# EMG_FSR.net
KiCad netlist of a schematic drawn in EAGLE
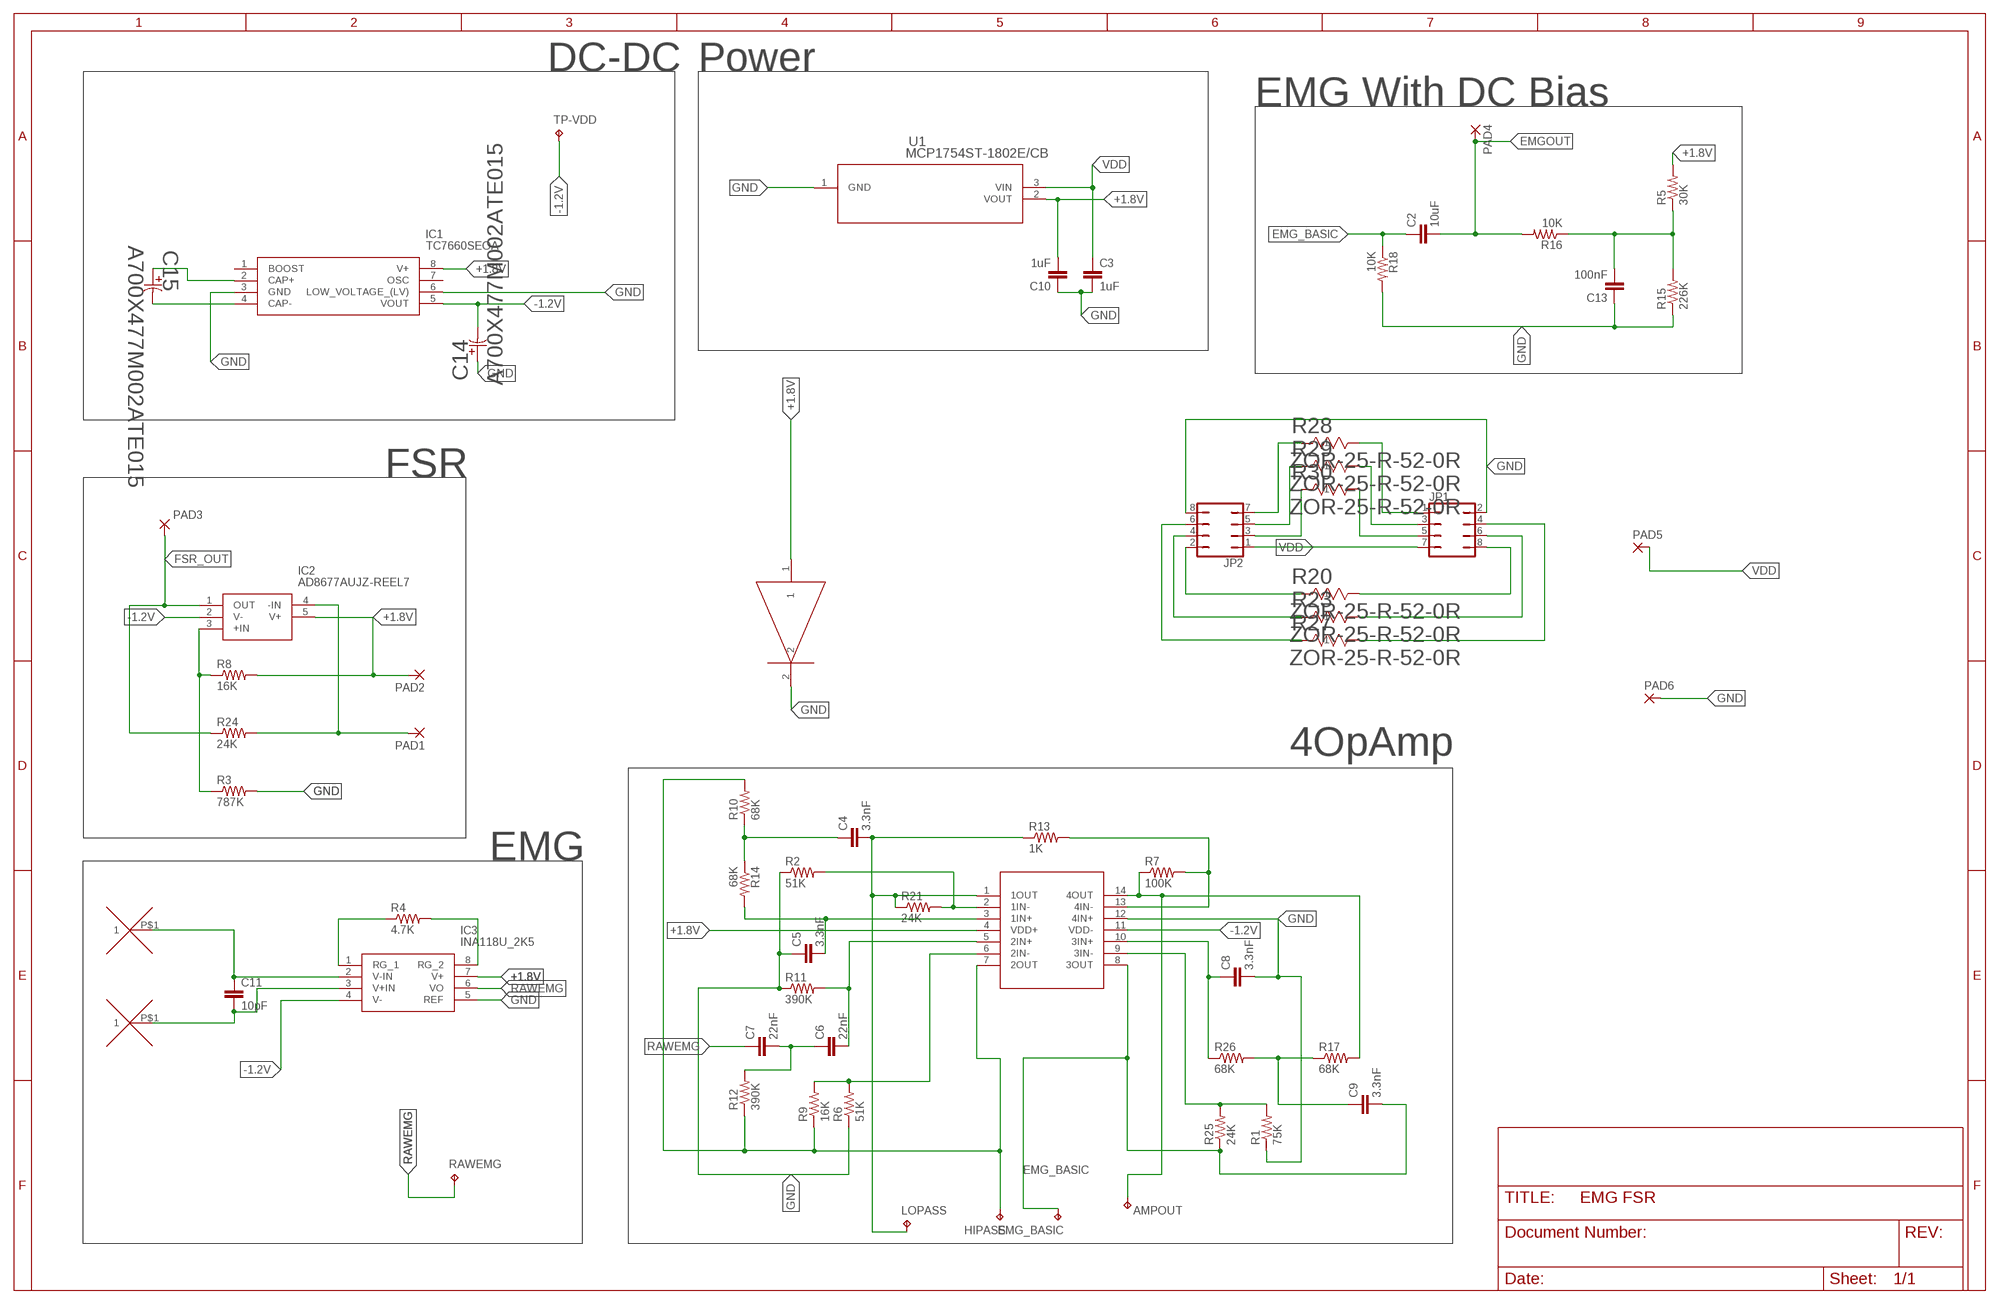
[diagram p0: schematic, sheet 1]

(export (version "E")
  (design (tool "Eeschema 10.0.6"))
  (components
    (comp (ref "AMPOUT")
      (value "TPTP08R")
      (footprint "eagle-import:TP08R")
      (libsource (lib "eagle-import") (part "TPTP08R"))
    )
    (comp (ref "C2")
      (value "10uF")
      (footprint "eagle-import:C0402")
      (libsource (lib "eagle-import") (part "rcl_334_C-EUC0402"))
    )
    (comp (ref "C3")
      (value "1uF")
      (footprint "eagle-import:C0402")
      (libsource (lib "eagle-import") (part "rcl_334_C-EUC0402"))
    )
    (comp (ref "C4")
      (value "3.3nF")
      (footprint "eagle-import:C1206")
      (libsource (lib "eagle-import") (part "C-EUC1206"))
    )
    (comp (ref "C5")
      (value "3.3nF")
      (footprint "eagle-import:C1206")
      (libsource (lib "eagle-import") (part "C-EUC1206"))
    )
    (comp (ref "C6")
      (value "22nF")
      (footprint "eagle-import:C0805")
      (libsource (lib "eagle-import") (part "C-EUC0805"))
    )
    (comp (ref "C7")
      (value "22nF")
      (footprint "eagle-import:C0805")
      (libsource (lib "eagle-import") (part "C-EUC0805"))
    )
    (comp (ref "C8")
      (value "3.3nF")
      (footprint "eagle-import:C1206")
      (libsource (lib "eagle-import") (part "C-EUC1206"))
    )
    (comp (ref "C9")
      (value "3.3nF")
      (footprint "eagle-import:C1206")
      (libsource (lib "eagle-import") (part "C-EUC1206"))
    )
    (comp (ref "C10")
      (value "1uF")
      (footprint "eagle-import:C0402")
      (libsource (lib "eagle-import") (part "rcl_334_C-EUC0402"))
    )
    (comp (ref "C11")
      (value "10pF")
      (footprint "eagle-import:C0402")
      (libsource (lib "eagle-import") (part "rcl_334_C-EUC0402"))
    )
    (comp (ref "C13")
      (value "100nF")
      (footprint "eagle-import:C0402")
      (libsource (lib "eagle-import") (part "rcl_334_C-EUC0402"))
    )
    (comp (ref "C14")
      (value "A700X477M002ATE015")
      (footprint "eagle-import:PCAP7343-43_KEMET_KEM")
      (libsource (lib "eagle-import") (part "A700X477M002ATE015"))
    )
    (comp (ref "C15")
      (value "A700X477M002ATE015")
      (footprint "eagle-import:PCAP7343-43_KEMET_KEM")
      (libsource (lib "eagle-import") (part "A700X477M002ATE015"))
    )
    (comp (ref "EMG_BASIC")
      (value "TPTP08R")
      (footprint "eagle-import:TP08R")
      (libsource (lib "eagle-import") (part "TPTP08R"))
    )
    (comp (ref "HIPASS")
      (value "TPTP08R")
      (footprint "eagle-import:TP08R")
      (libsource (lib "eagle-import") (part "TPTP08R"))
    )
    (comp (ref "IC1")
      (value "TC7660SEOA")
      (footprint "eagle-import:SOIC127P600X175-8N")
      (fields (field (name "MOUSER_PART_NUMBER") "579-TC7660SEOA"))
      (libsource (lib "eagle-import") (part "TC7660SEOA"))
    )
    (comp (ref "IC2")
      (value "AD8677AUJZ-REEL7")
      (footprint "eagle-import:SOT95P280X100-5N")
      (fields (field (name "MOUSER_PART_NUMBER") "584-AD8677AUJZ-R7"))
      (libsource (lib "eagle-import") (part "AD8677AUJZ-REEL7"))
    )
    (comp (ref "IC3")
      (value "INA118U_2K5")
      (footprint "eagle-import:SOIC127P600X175-8N")
      (fields
        (field (name "ARROW_PART_NUMBER") "INA118U/2K5")
        (field (name "MOUSER_PART_NUMBER") "595-INA118U/2K5")
      )
      (libsource (lib "eagle-import") (part "INA118U_2K5"))
    )
    (comp (ref "JP1")
      (value "JP4Q")
      (footprint "eagle-import:JP4Q")
      (libsource (lib "eagle-import") (part "JP4Q"))
    )
    (comp (ref "JP2")
      (value "JP4Q")
      (footprint "eagle-import:JP4Q")
      (libsource (lib "eagle-import") (part "JP4Q"))
    )
    (comp (ref "LOPASS")
      (value "TPTP08R")
      (footprint "eagle-import:TP08R")
      (libsource (lib "eagle-import") (part "TPTP08R"))
    )
    (comp (ref "PAD1")
      (value "SMD2")
      (footprint "eagle-import:SMD1,27-2,54")
      (libsource (lib "eagle-import") (part "SMD2"))
    )
    (comp (ref "PAD2")
      (value "SMD2")
      (footprint "eagle-import:SMD1,27-2,54")
      (libsource (lib "eagle-import") (part "SMD2"))
    )
    (comp (ref "PAD3")
      (value "1,6/0,8")
      (footprint "eagle-import:1,6_0,8")
      (libsource (lib "eagle-import") (part "1,6/0,8"))
    )
    (comp (ref "PAD4")
      (value "1,6/0,8")
      (footprint "eagle-import:1,6_0,8")
      (libsource (lib "eagle-import") (part "1,6/0,8"))
    )
    (comp (ref "PAD5")
      (value "1,6/0,8")
      (footprint "eagle-import:1,6_0,8")
      (libsource (lib "eagle-import") (part "1,6/0,8"))
    )
    (comp (ref "PAD6")
      (value "1,6/0,8")
      (footprint "eagle-import:1,6_0,8")
      (libsource (lib "eagle-import") (part "1,6/0,8"))
    )
    (comp (ref "R1")
      (value "75K")
      (footprint "eagle-import:R0402")
      (libsource (lib "eagle-import") (part "adafruit_420_R-US_R0402"))
    )
    (comp (ref "R2")
      (value "51K")
      (footprint "eagle-import:R0402")
      (libsource (lib "eagle-import") (part "adafruit_420_R-US_R0402"))
    )
    (comp (ref "R3")
      (value "787K")
      (footprint "eagle-import:R0805")
      (libsource (lib "eagle-import") (part "rcl_R-US_R0805"))
    )
    (comp (ref "R4")
      (value "4.7K")
      (footprint "eagle-import:R0402")
      (libsource (lib "eagle-import") (part "adafruit@1_R-US_R0402"))
    )
    (comp (ref "R5")
      (value "30K")
      (footprint "eagle-import:R0402")
      (libsource (lib "eagle-import") (part "adafruit_420_R-US_R0402"))
    )
    (comp (ref "R6")
      (value "51K")
      (footprint "eagle-import:R0402")
      (libsource (lib "eagle-import") (part "adafruit_420_R-US_R0402"))
    )
    (comp (ref "R7")
      (value "100K")
      (footprint "eagle-import:R1005")
      (libsource (lib "eagle-import") (part "adafruit@1_R-US_R1005"))
    )
    (comp (ref "R8")
      (value "16K")
      (footprint "eagle-import:R0402")
      (libsource (lib "eagle-import") (part "adafruit_420_R-US_R0402"))
    )
    (comp (ref "R9")
      (value "16K")
      (footprint "eagle-import:R0402")
      (libsource (lib "eagle-import") (part "adafruit_420_R-US_R0402"))
    )
    (comp (ref "R10")
      (value "68K")
      (footprint "eagle-import:R0402")
      (libsource (lib "eagle-import") (part "adafruit_420_R-US_R0402"))
    )
    (comp (ref "R11")
      (value "390K")
      (footprint "eagle-import:R0603")
      (libsource (lib "eagle-import") (part "R-US_R0603"))
    )
    (comp (ref "R12")
      (value "390K")
      (footprint "eagle-import:R0603")
      (libsource (lib "eagle-import") (part "adafruit@1_R-US_R0603"))
    )
    (comp (ref "R13")
      (value "1K")
      (footprint "eagle-import:R0402")
      (libsource (lib "eagle-import") (part "adafruit_420_R-US_R0402"))
    )
    (comp (ref "R14")
      (value "68K")
      (footprint "eagle-import:R0402")
      (libsource (lib "eagle-import") (part "adafruit_420_R-US_R0402"))
    )
    (comp (ref "R15")
      (value "226K")
      (footprint "eagle-import:R0402")
      (libsource (lib "eagle-import") (part "adafruit_420_R-US_R0402"))
    )
    (comp (ref "R16")
      (value "10K")
      (footprint "eagle-import:R0402")
      (libsource (lib "eagle-import") (part "adafruit_420_R-US_R0402"))
    )
    (comp (ref "R17")
      (value "68K")
      (footprint "eagle-import:R0402")
      (libsource (lib "eagle-import") (part "adafruit_420_R-US_R0402"))
    )
    (comp (ref "R18")
      (value "10K")
      (footprint "eagle-import:R0402")
      (libsource (lib "eagle-import") (part "adafruit_420_R-US_R0402"))
    )
    (comp (ref "R20")
      (value "ZOR-25-R-52-0R")
      (footprint "eagle-import:RES_ZOR25_6P3X2P3_YAG")
      (fields (field (name "COPYRIGHT") "Copyright (C) 2018 Accelerated Designs. All rights reserved"))
      (libsource (lib "eagle-import") (part "ZOR-25-R-52-0R"))
    )
    (comp (ref "R21")
      (value "24K")
      (footprint "eagle-import:R0402")
      (libsource (lib "eagle-import") (part "adafruit_420_R-US_R0402"))
    )
    (comp (ref "R23")
      (value "ZOR-25-R-52-0R")
      (footprint "eagle-import:RES_ZOR25_6P3X2P3_YAG")
      (fields (field (name "COPYRIGHT") "Copyright (C) 2018 Accelerated Designs. All rights reserved"))
      (libsource (lib "eagle-import") (part "ZOR-25-R-52-0R"))
    )
    (comp (ref "R24")
      (value "24K")
      (footprint "eagle-import:R0402")
      (libsource (lib "eagle-import") (part "adafruit_420_R-US_R0402"))
    )
    (comp (ref "R25")
      (value "24K")
      (footprint "eagle-import:R0402")
      (libsource (lib "eagle-import") (part "adafruit_420_R-US_R0402"))
    )
    (comp (ref "R26")
      (value "68K")
      (footprint "eagle-import:R0402")
      (libsource (lib "eagle-import") (part "adafruit_420_R-US_R0402"))
    )
    (comp (ref "R27")
      (value "ZOR-25-R-52-0R")
      (footprint "eagle-import:RES_ZOR25_6P3X2P3_YAG")
      (fields (field (name "COPYRIGHT") "Copyright (C) 2018 Accelerated Designs. All rights reserved"))
      (libsource (lib "eagle-import") (part "ZOR-25-R-52-0R"))
    )
    (comp (ref "R28")
      (value "ZOR-25-R-52-0R")
      (footprint "eagle-import:RES_ZOR25_6P3X2P3_YAG")
      (fields (field (name "COPYRIGHT") "Copyright (C) 2018 Accelerated Designs. All rights reserved"))
      (libsource (lib "eagle-import") (part "ZOR-25-R-52-0R"))
    )
    (comp (ref "R29")
      (value "ZOR-25-R-52-0R")
      (footprint "eagle-import:RES_ZOR25_6P3X2P3_YAG")
      (fields (field (name "COPYRIGHT") "Copyright (C) 2018 Accelerated Designs. All rights reserved"))
      (libsource (lib "eagle-import") (part "ZOR-25-R-52-0R"))
    )
    (comp (ref "R30")
      (value "ZOR-25-R-52-0R")
      (footprint "eagle-import:RES_ZOR25_6P3X2P3_YAG")
      (fields (field (name "COPYRIGHT") "Copyright (C) 2018 Accelerated Designs. All rights reserved"))
      (libsource (lib "eagle-import") (part "ZOR-25-R-52-0R"))
    )
    (comp (ref "RAWEMG")
      (value "TPTP08R")
      (footprint "eagle-import:TP08R")
      (libsource (lib "eagle-import") (part "TPTP08R"))
    )
    (comp (ref "RED")
      (value "RESC0402X40N")
      (footprint "eagle-import:RESC0402X40N")
      (fields (field (name "MANUFACTURER") "KOA"))
      (libsource (lib "eagle-import") (part "RESC0402X40N"))
    )
    (comp (ref "TP-VDD")
      (value "TPTP08R")
      (footprint "eagle-import:TP08R")
      (libsource (lib "eagle-import") (part "TPTP08R"))
    )
    (comp (ref "U$1")
      (value "TLC2274-HT")
      (footprint "eagle-import:SOP65P640X120-14N")
      (libsource (lib "eagle-import") (part "TLC2274-HT"))
    )
    (comp (ref "U$2")
      (value "EMG_VIA")
      (footprint "eagle-import:EMG_VIA")
      (libsource (lib "eagle-import") (part "EMG_VIA"))
    )
    (comp (ref "U$3")
      (value "EMG_VIA")
      (footprint "eagle-import:EMG_VIA")
      (libsource (lib "eagle-import") (part "EMG_VIA"))
    )
    (comp (ref "U1")
      (value "MCP1754ST-1802E/CB")
      (footprint "eagle-import:SOT-23A_MC_MCH")
      (fields (field (name "COPYRIGHT") "Copyright (C) 2018 Accelerated Designs. All rights reserved"))
      (libsource (lib "eagle-import") (part "MCP1754ST-1802E/CB"))
    )
  )
  (nets
    (net (code "1") (name "+1.8V") (class "Default")
      (node (ref "C10") (pin "2") (pinfunction "2_2") (pintype "passive"))
      (node (ref "IC1") (pin "8") (pinfunction "V+_8") (pintype "bidirectional"))
      (node (ref "IC2") (pin "5") (pinfunction "V+_5") (pintype "bidirectional"))
      (node (ref "IC3") (pin "7") (pinfunction "V+_7") (pintype "bidirectional"))
      (node (ref "PAD2") (pin "1") (pinfunction "P_1") (pintype "passive"))
      (node (ref "R5") (pin "2") (pinfunction "2_2") (pintype "passive"))
      (node (ref "R8") (pin "2") (pinfunction "2_2") (pintype "passive"))
      (node (ref "RED") (pin "1") (pinfunction "1_1") (pintype "bidirectional"))
      (node (ref "U$1") (pin "4") (pinfunction "VDD+_4") (pintype "bidirectional"))
      (node (ref "U1") (pin "2") (pinfunction "VOUT_2") (pintype "output"))
    )
    (net (code "2") (name "-1.2V") (class "Default")
      (node (ref "C14") (pin "2") (pinfunction "2_2") (pintype "passive"))
      (node (ref "IC1") (pin "5") (pinfunction "VOUT_5") (pintype "bidirectional"))
      (node (ref "IC2") (pin "2") (pinfunction "V-_2") (pintype "bidirectional"))
      (node (ref "IC3") (pin "4") (pinfunction "V-_4") (pintype "bidirectional"))
      (node (ref "TP-VDD") (pin "TP") (pinfunction "TP_TP") (pintype "input"))
      (node (ref "U$1") (pin "11") (pinfunction "VDD-_11") (pintype "bidirectional"))
    )
    (net (code "3") (name "EMGOUT") (class "Default")
      (node (ref "C2") (pin "2") (pinfunction "2_2") (pintype "passive"))
      (node (ref "PAD4") (pin "1") (pinfunction "P_1") (pintype "passive"))
      (node (ref "R16") (pin "2") (pinfunction "2_2") (pintype "passive"))
    )
    (net (code "4") (name "EMG_BASIC") (class "Default")
      (node (ref "C2") (pin "1") (pinfunction "1_1") (pintype "passive"))
      (node (ref "C9") (pin "2") (pinfunction "2_2") (pintype "passive"))
      (node (ref "EMG_BASIC") (pin "TP") (pinfunction "TP_TP") (pintype "input"))
      (node (ref "R18") (pin "1") (pinfunction "1_1") (pintype "passive"))
      (node (ref "R25") (pin "1") (pinfunction "1_1") (pintype "passive"))
      (node (ref "U$1") (pin "8") (pinfunction "3OUT_8") (pintype "bidirectional"))
    )
    (net (code "5") (name "FSR_OUT") (class "Default")
      (node (ref "IC2") (pin "1") (pinfunction "OUT_1") (pintype "output"))
      (node (ref "PAD3") (pin "1") (pinfunction "P_1") (pintype "passive"))
      (node (ref "R24") (pin "1") (pinfunction "1_1") (pintype "passive"))
    )
    (net (code "6") (name "GND") (class "Default")
      (node (ref "C10") (pin "1") (pinfunction "1_1") (pintype "passive"))
      (node (ref "C13") (pin "1") (pinfunction "1_1") (pintype "passive"))
      (node (ref "C14") (pin "1") (pinfunction "1_1") (pintype "passive"))
      (node (ref "C3") (pin "2") (pinfunction "2_2") (pintype "passive"))
      (node (ref "C5") (pin "1") (pinfunction "1_1") (pintype "passive"))
      (node (ref "C8") (pin "2") (pinfunction "2_2") (pintype "passive"))
      (node (ref "IC1") (pin "3") (pinfunction "GND_3") (pintype "bidirectional"))
      (node (ref "IC1") (pin "6") (pinfunction "LOW_VOLTAGE_(LV)_6") (pintype "bidirectional"))
      (node (ref "IC3") (pin "5") (pinfunction "REF_5") (pintype "bidirectional"))
      (node (ref "JP1") (pin "2") (pinfunction "2_2") (pintype "passive"))
      (node (ref "JP2") (pin "8") (pinfunction "8_8") (pintype "passive"))
      (node (ref "PAD6") (pin "1") (pinfunction "P_1") (pintype "passive"))
      (node (ref "R1") (pin "1") (pinfunction "1_1") (pintype "passive"))
      (node (ref "R11") (pin "1") (pinfunction "1_1") (pintype "passive"))
      (node (ref "R15") (pin "1") (pinfunction "1_1") (pintype "passive"))
      (node (ref "R18") (pin "2") (pinfunction "2_2") (pintype "passive"))
      (node (ref "R2") (pin "1") (pinfunction "1_1") (pintype "passive"))
      (node (ref "R3") (pin "2") (pinfunction "2_2") (pintype "passive"))
      (node (ref "R6") (pin "1") (pinfunction "1_1") (pintype "passive"))
      (node (ref "RED") (pin "2") (pinfunction "2_2") (pintype "bidirectional"))
      (node (ref "U$1") (pin "12") (pinfunction "4IN+_12") (pintype "bidirectional"))
      (node (ref "U1") (pin "1") (pinfunction "GND_1") (pintype "power_in"))
    )
    (net (code "7") (name "Net-(C4-Pad1)") (class "Default")
      (node (ref "C4") (pin "1") (pinfunction "1_1") (pintype "passive"))
      (node (ref "R10") (pin "1") (pinfunction "1_1") (pintype "passive"))
      (node (ref "R14") (pin "1") (pinfunction "1_1") (pintype "passive"))
    )
    (net (code "8") (name "Net-(C6-Pad1)") (class "Default")
      (node (ref "C6") (pin "1") (pinfunction "1_1") (pintype "passive"))
      (node (ref "C7") (pin "2") (pinfunction "2_2") (pintype "passive"))
      (node (ref "R12") (pin "2") (pinfunction "2_2") (pintype "passive"))
    )
    (net (code "9") (name "Net-(C9-Pad1)") (class "Default")
      (node (ref "C9") (pin "1") (pinfunction "1_1") (pintype "passive"))
      (node (ref "R17") (pin "1") (pinfunction "1_1") (pintype "passive"))
      (node (ref "R26") (pin "2") (pinfunction "2_2") (pintype "passive"))
    )
    (net (code "10") (name "Net-(C13-Pad2)") (class "Default")
      (node (ref "C13") (pin "2") (pinfunction "2_2") (pintype "passive"))
      (node (ref "R15") (pin "2") (pinfunction "2_2") (pintype "passive"))
      (node (ref "R16") (pin "1") (pinfunction "1_1") (pintype "passive"))
      (node (ref "R5") (pin "1") (pinfunction "1_1") (pintype "passive"))
    )
    (net (code "11") (name "Net-(IC1-CAP+)") (class "Default")
      (node (ref "C15") (pin "1") (pinfunction "1_1") (pintype "passive"))
      (node (ref "IC1") (pin "2") (pinfunction "CAP+_2") (pintype "bidirectional"))
    )
    (net (code "12") (name "Net-(IC1-CAP-)") (class "Default")
      (node (ref "C15") (pin "2") (pinfunction "2_2") (pintype "passive"))
      (node (ref "IC1") (pin "4") (pinfunction "CAP-_4") (pintype "bidirectional"))
    )
    (net (code "13") (name "Net-(IC2-+IN)") (class "Default")
      (node (ref "IC2") (pin "3") (pinfunction "+IN_3") (pintype "input"))
      (node (ref "R3") (pin "1") (pinfunction "1_1") (pintype "passive"))
      (node (ref "R8") (pin "1") (pinfunction "1_1") (pintype "passive"))
    )
    (net (code "14") (name "Net-(IC2--IN)") (class "Default")
      (node (ref "IC2") (pin "4") (pinfunction "-IN_4") (pintype "input"))
      (node (ref "PAD1") (pin "1") (pinfunction "P_1") (pintype "passive"))
      (node (ref "R24") (pin "2") (pinfunction "2_2") (pintype "passive"))
    )
    (net (code "15") (name "Net-(IC3-RG_1)") (class "Default")
      (node (ref "IC3") (pin "1") (pinfunction "RG_1_1") (pintype "bidirectional"))
      (node (ref "R4") (pin "1") (pinfunction "1_1") (pintype "passive"))
    )
    (net (code "16") (name "Net-(IC3-RG_2)") (class "Default")
      (node (ref "IC3") (pin "8") (pinfunction "RG_2_8") (pintype "bidirectional"))
      (node (ref "R4") (pin "2") (pinfunction "2_2") (pintype "passive"))
    )
    (net (code "17") (name "Net-(IC3-V+IN)") (class "Default")
      (node (ref "C11") (pin "2") (pinfunction "2_2") (pintype "passive"))
      (node (ref "IC3") (pin "3") (pinfunction "V+IN_3") (pintype "bidirectional"))
      (node (ref "U$3") (pin "P$1") (pinfunction "1_P$1") (pintype "bidirectional"))
    )
    (net (code "18") (name "Net-(IC3-V-IN)") (class "Default")
      (node (ref "C11") (pin "1") (pinfunction "1_1") (pintype "passive"))
      (node (ref "IC3") (pin "2") (pinfunction "V-IN_2") (pintype "bidirectional"))
      (node (ref "U$2") (pin "P$1") (pinfunction "1_P$1") (pintype "bidirectional"))
    )
    (net (code "19") (name "Net-(JP1-Pad1)") (class "Default")
      (node (ref "JP1") (pin "1") (pinfunction "1_1") (pintype "passive"))
      (node (ref "R28") (pin "2") (pinfunction "2_2") (pintype "passive"))
    )
    (net (code "20") (name "Net-(JP1-Pad3)") (class "Default")
      (node (ref "JP1") (pin "3") (pinfunction "3_3") (pintype "passive"))
      (node (ref "R29") (pin "2") (pinfunction "2_2") (pintype "passive"))
    )
    (net (code "21") (name "Net-(JP1-Pad4)") (class "Default")
      (node (ref "JP1") (pin "4") (pinfunction "4_4") (pintype "passive"))
      (node (ref "R27") (pin "2") (pinfunction "2_2") (pintype "passive"))
    )
    (net (code "22") (name "Net-(JP1-Pad5)") (class "Default")
      (node (ref "JP1") (pin "5") (pinfunction "5_5") (pintype "passive"))
      (node (ref "R30") (pin "2") (pinfunction "2_2") (pintype "passive"))
    )
    (net (code "23") (name "Net-(JP1-Pad6)") (class "Default")
      (node (ref "JP1") (pin "6") (pinfunction "6_6") (pintype "passive"))
      (node (ref "R23") (pin "2") (pinfunction "2_2") (pintype "passive"))
    )
    (net (code "24") (name "Net-(JP1-Pad8)") (class "Default")
      (node (ref "JP1") (pin "8") (pinfunction "8_8") (pintype "passive"))
      (node (ref "R20") (pin "2") (pinfunction "2_2") (pintype "passive"))
    )
    (net (code "25") (name "Net-(JP2-Pad2)") (class "Default")
      (node (ref "JP2") (pin "2") (pinfunction "2_2") (pintype "passive"))
      (node (ref "R20") (pin "1") (pinfunction "1_1") (pintype "passive"))
    )
    (net (code "26") (name "Net-(JP2-Pad3)") (class "Default")
      (node (ref "JP2") (pin "3") (pinfunction "3_3") (pintype "passive"))
      (node (ref "R30") (pin "1") (pinfunction "1_1") (pintype "passive"))
    )
    (net (code "27") (name "Net-(JP2-Pad4)") (class "Default")
      (node (ref "JP2") (pin "4") (pinfunction "4_4") (pintype "passive"))
      (node (ref "R23") (pin "1") (pinfunction "1_1") (pintype "passive"))
    )
    (net (code "28") (name "Net-(JP2-Pad5)") (class "Default")
      (node (ref "JP2") (pin "5") (pinfunction "5_5") (pintype "passive"))
      (node (ref "R29") (pin "1") (pinfunction "1_1") (pintype "passive"))
    )
    (net (code "29") (name "Net-(JP2-Pad6)") (class "Default")
      (node (ref "JP2") (pin "6") (pinfunction "6_6") (pintype "passive"))
      (node (ref "R27") (pin "1") (pinfunction "1_1") (pintype "passive"))
    )
    (net (code "30") (name "Net-(JP2-Pad7)") (class "Default")
      (node (ref "JP2") (pin "7") (pinfunction "7_7") (pintype "passive"))
      (node (ref "R28") (pin "1") (pinfunction "1_1") (pintype "passive"))
    )
    (net (code "31") (name "Net-(U$1-1IN+)") (class "Default")
      (node (ref "C5") (pin "2") (pinfunction "2_2") (pintype "passive"))
      (node (ref "R14") (pin "2") (pinfunction "2_2") (pintype "passive"))
      (node (ref "U$1") (pin "3") (pinfunction "1IN+_3") (pintype "bidirectional"))
    )
    (net (code "32") (name "Net-(U$1-1IN-)") (class "Default")
      (node (ref "R2") (pin "2") (pinfunction "2_2") (pintype "passive"))
      (node (ref "R21") (pin "2") (pinfunction "2_2") (pintype "passive"))
      (node (ref "U$1") (pin "2") (pinfunction "1IN-_2") (pintype "bidirectional"))
    )
    (net (code "33") (name "Net-(U$1-1OUT)") (class "Default")
      (node (ref "C4") (pin "2") (pinfunction "2_2") (pintype "passive"))
      (node (ref "LOPASS") (pin "TP") (pinfunction "TP_TP") (pintype "input"))
      (node (ref "R13") (pin "1") (pinfunction "1_1") (pintype "passive"))
      (node (ref "R21") (pin "1") (pinfunction "1_1") (pintype "passive"))
      (node (ref "U$1") (pin "1") (pinfunction "1OUT_1") (pintype "bidirectional"))
    )
    (net (code "34") (name "Net-(U$1-2IN+)") (class "Default")
      (node (ref "C6") (pin "2") (pinfunction "2_2") (pintype "passive"))
      (node (ref "R11") (pin "2") (pinfunction "2_2") (pintype "passive"))
      (node (ref "U$1") (pin "5") (pinfunction "2IN+_5") (pintype "bidirectional"))
    )
    (net (code "35") (name "Net-(U$1-2IN-)") (class "Default")
      (node (ref "R6") (pin "2") (pinfunction "2_2") (pintype "passive"))
      (node (ref "R9") (pin "2") (pinfunction "2_2") (pintype "passive"))
      (node (ref "U$1") (pin "6") (pinfunction "2IN-_6") (pintype "bidirectional"))
    )
    (net (code "36") (name "Net-(U$1-2OUT)") (class "Default")
      (node (ref "HIPASS") (pin "TP") (pinfunction "TP_TP") (pintype "input"))
      (node (ref "R10") (pin "2") (pinfunction "2_2") (pintype "passive"))
      (node (ref "R12") (pin "1") (pinfunction "1_1") (pintype "passive"))
      (node (ref "R9") (pin "1") (pinfunction "1_1") (pintype "passive"))
      (node (ref "U$1") (pin "7") (pinfunction "2OUT_7") (pintype "bidirectional"))
    )
    (net (code "37") (name "Net-(U$1-3IN+)") (class "Default")
      (node (ref "C8") (pin "1") (pinfunction "1_1") (pintype "passive"))
      (node (ref "R26") (pin "1") (pinfunction "1_1") (pintype "passive"))
      (node (ref "U$1") (pin "10") (pinfunction "3IN+_10") (pintype "bidirectional"))
    )
    (net (code "38") (name "Net-(U$1-3IN-)") (class "Default")
      (node (ref "R1") (pin "2") (pinfunction "2_2") (pintype "passive"))
      (node (ref "R25") (pin "2") (pinfunction "2_2") (pintype "passive"))
      (node (ref "U$1") (pin "9") (pinfunction "3IN-_9") (pintype "bidirectional"))
    )
    (net (code "39") (name "Net-(U$1-4IN-)") (class "Default")
      (node (ref "R13") (pin "2") (pinfunction "2_2") (pintype "passive"))
      (node (ref "R7") (pin "2") (pinfunction "2_2") (pintype "passive"))
      (node (ref "U$1") (pin "13") (pinfunction "4IN-_13") (pintype "bidirectional"))
    )
    (net (code "40") (name "Net-(U$1-4OUT)") (class "Default")
      (node (ref "AMPOUT") (pin "TP") (pinfunction "TP_TP") (pintype "input"))
      (node (ref "R17") (pin "2") (pinfunction "2_2") (pintype "passive"))
      (node (ref "R7") (pin "1") (pinfunction "1_1") (pintype "passive"))
      (node (ref "U$1") (pin "14") (pinfunction "4OUT_14") (pintype "bidirectional"))
    )
    (net (code "41") (name "RAWEMG") (class "Default")
      (node (ref "C7") (pin "1") (pinfunction "1_1") (pintype "passive"))
      (node (ref "IC3") (pin "6") (pinfunction "VO_6") (pintype "bidirectional"))
      (node (ref "RAWEMG") (pin "TP") (pinfunction "TP_TP") (pintype "input"))
    )
    (net (code "42") (name "VDD") (class "Default")
      (node (ref "C3") (pin "1") (pinfunction "1_1") (pintype "passive"))
      (node (ref "JP1") (pin "7") (pinfunction "7_7") (pintype "passive"))
      (node (ref "JP2") (pin "1") (pinfunction "1_1") (pintype "passive"))
      (node (ref "PAD5") (pin "1") (pinfunction "P_1") (pintype "passive"))
      (node (ref "U1") (pin "3") (pinfunction "VIN_3") (pintype "input"))
    )
    (net (code "43") (name "unconnected-(IC1-BOOST-Pad1)") (class "Default")
      (node (ref "IC1") (pin "1") (pinfunction "BOOST_1") (pintype "bidirectional"))
    )
    (net (code "44") (name "unconnected-(IC1-OSC-Pad7)") (class "Default")
      (node (ref "IC1") (pin "7") (pinfunction "OSC_7") (pintype "bidirectional"))
    )
  )
)
